# EndLightGate2022.net
KiCad netlist of a schematic drawn in EAGLE
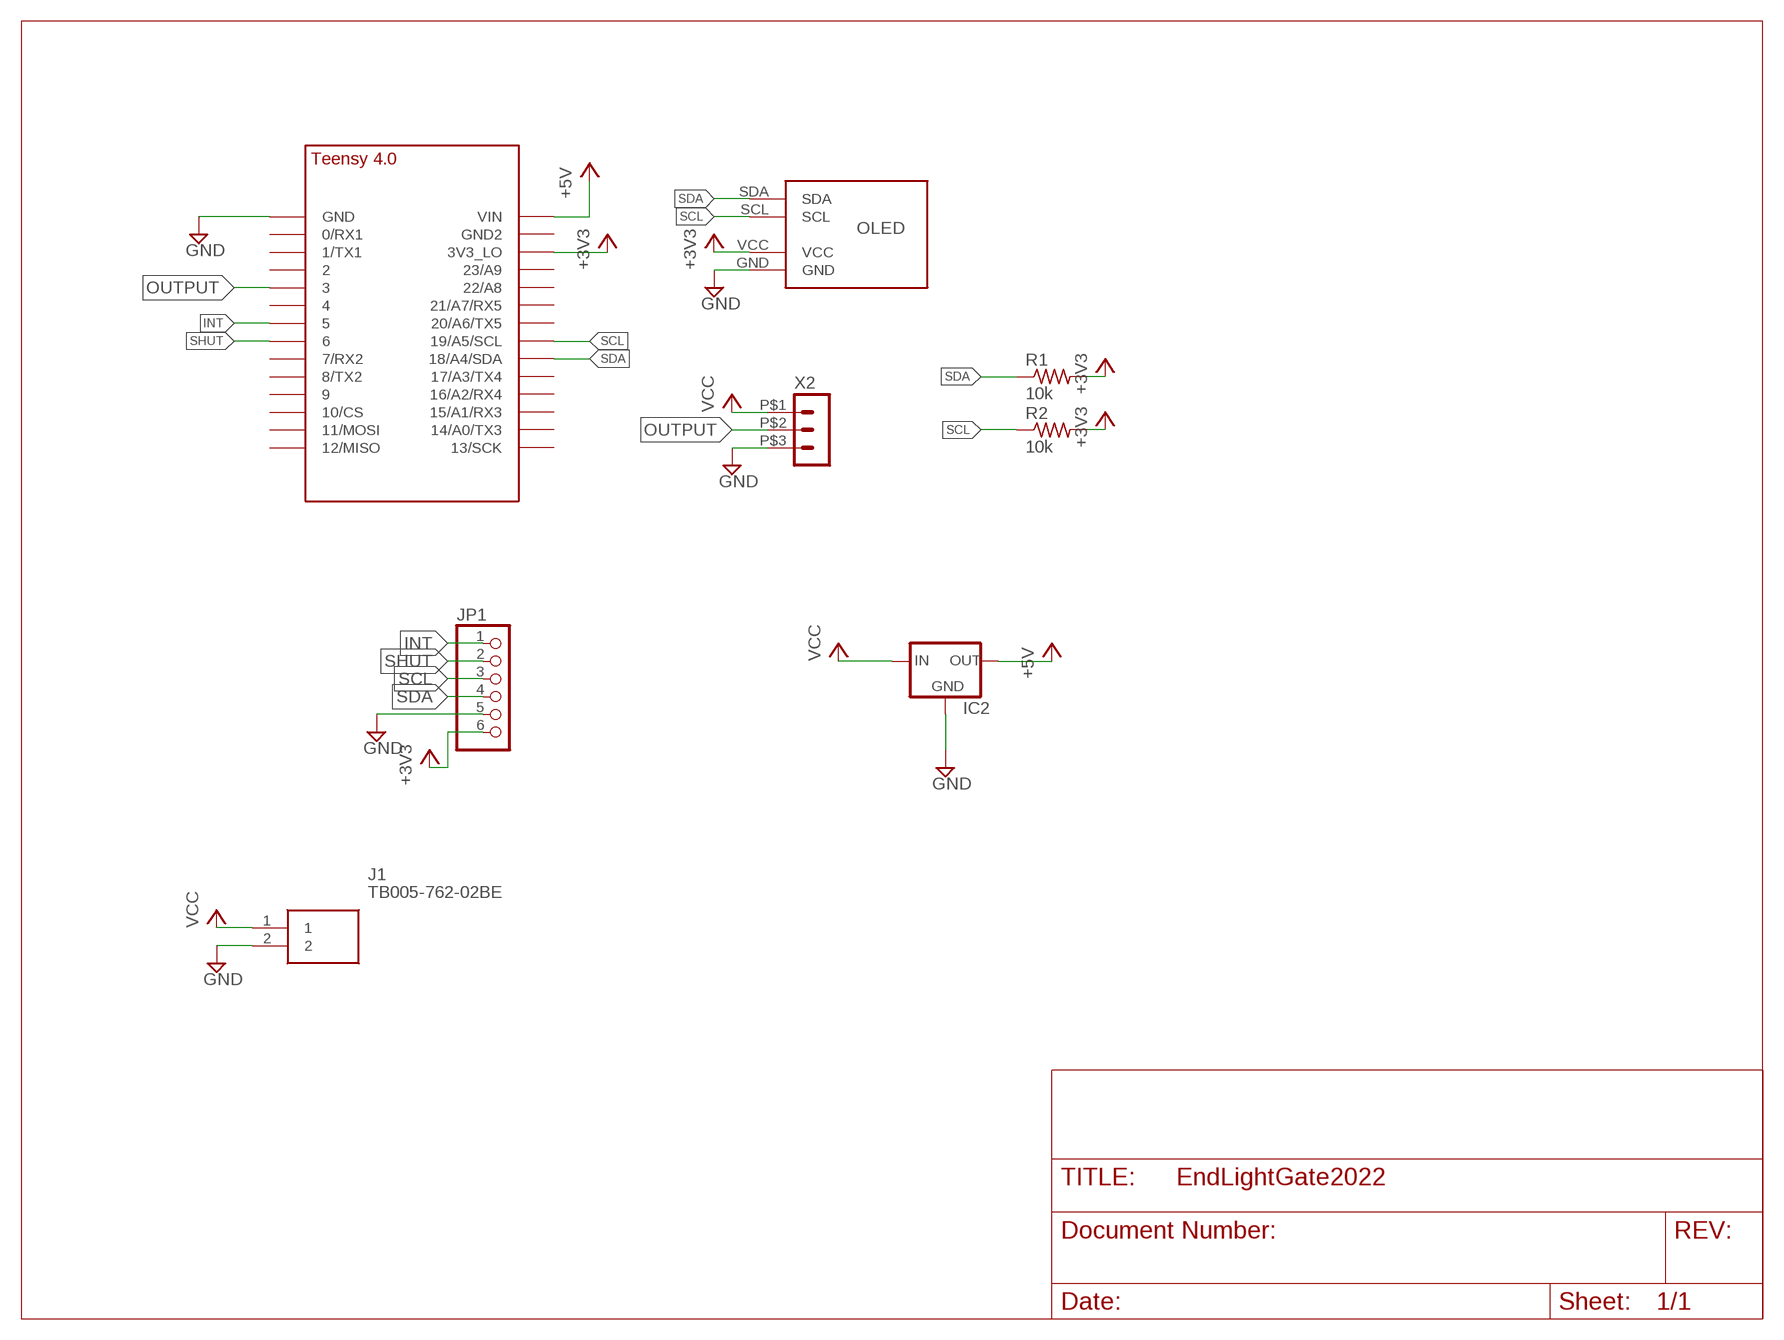
[diagram p0: schematic, sheet 1]

(export (version "E")
  (design (tool "Eeschema 10.0.6"))
  (components
    (comp (ref "IC2")
      (value "REG_5V_L7805_HOR")
      (footprint "eagle-import:TO-220-H")
      (libsource (lib "eagle-import") (part "REG_5V_L7805_HOR"))
    )
    (comp (ref "J1")
      (value "TB005-762-02BE")
      (footprint "eagle-import:TB00576202BE")
      (fields (field (name "MOUSER_PART_NUMBER") "490-TB005-762-02BE"))
      (libsource (lib "eagle-import") (part "TB005-762-02BE"))
    )
    (comp (ref "JP1")
      (value "PINHD-1X6")
      (footprint "eagle-import:1X06")
      (libsource (lib "eagle-import") (part "PINHD-1X6"))
    )
    (comp (ref "R1")
      (value "10k")
      (footprint "eagle-import:1_4W-0.4")
      (libsource (lib "eagle-import") (part "RES_AXIAL1/4W-0.4"))
    )
    (comp (ref "R2")
      (value "10k")
      (footprint "eagle-import:1_4W-0.4")
      (libsource (lib "eagle-import") (part "RES_AXIAL1/4W-0.4"))
    )
    (comp (ref "U$1")
      (value "TEENSY_4.0_SIMPLE")
      (footprint "eagle-import:TEENSY_4.0_SIMPLE")
      (libsource (lib "eagle-import") (part "TEENSY_4.0_SIMPLE"))
    )
    (comp (ref "U$2")
      (value "OLED_SSD1306")
      (footprint "eagle-import:OLED_SSD1306")
      (libsource (lib "eagle-import") (part "OLED_SSD1306"))
    )
    (comp (ref "X2")
      (value "HEADER_POS3_43650-0300")
      (footprint "eagle-import:43650-0300")
      (libsource (lib "eagle-import") (part "HEADER_POS3_?43650-0300"))
    )
  )
  (nets
    (net (code "1") (name "+3V3") (class "Default")
      (node (ref "JP1") (pin "6") (pinfunction "6_6") (pintype "passive"))
      (node (ref "R1") (pin "2") (pinfunction "2_2") (pintype "passive"))
      (node (ref "R2") (pin "2") (pinfunction "2_2") (pintype "passive"))
      (node (ref "U$1") (pin "3V3_LO") (pinfunction "3V3_LO_3V3_LO") (pintype "bidirectional"))
      (node (ref "U$2") (pin "VCC") (pinfunction "VCC_VCC") (pintype "bidirectional"))
    )
    (net (code "2") (name "+5V") (class "Default")
      (node (ref "IC2") (pin "3") (pinfunction "OUT_3") (pintype "output"))
      (node (ref "U$1") (pin "VIN") (pinfunction "VIN_VIN") (pintype "bidirectional"))
    )
    (net (code "3") (name "GND") (class "Default")
      (node (ref "IC2") (pin "2") (pinfunction "GND_2") (pintype "input"))
      (node (ref "J1") (pin "2") (pinfunction "2_2") (pintype "bidirectional"))
      (node (ref "JP1") (pin "5") (pinfunction "5_5") (pintype "passive"))
      (node (ref "U$1") (pin "GND") (pinfunction "GND_GND") (pintype "bidirectional"))
      (node (ref "U$2") (pin "GND") (pinfunction "GND_GND") (pintype "bidirectional"))
      (node (ref "X2") (pin "P$3") (pinfunction "3_P$3") (pintype "passive"))
    )
    (net (code "4") (name "INT") (class "Default")
      (node (ref "JP1") (pin "1") (pinfunction "1_1") (pintype "passive"))
      (node (ref "U$1") (pin "5") (pinfunction "5_5") (pintype "bidirectional"))
    )
    (net (code "5") (name "OUTPUT") (class "Default")
      (node (ref "U$1") (pin "3/CANTX") (pinfunction "3_3/CANTX") (pintype "bidirectional"))
      (node (ref "X2") (pin "P$2") (pinfunction "2_P$2") (pintype "passive"))
    )
    (net (code "6") (name "SCL") (class "Default")
      (node (ref "JP1") (pin "3") (pinfunction "3_3") (pintype "passive"))
      (node (ref "R2") (pin "1") (pinfunction "1_1") (pintype "passive"))
      (node (ref "U$1") (pin "19/A5/SCL") (pinfunction "19/A5/SCL_19/A5/SCL") (pintype "bidirectional"))
      (node (ref "U$2") (pin "SCL") (pinfunction "SCL_SCL") (pintype "bidirectional"))
    )
    (net (code "7") (name "SDA") (class "Default")
      (node (ref "JP1") (pin "4") (pinfunction "4_4") (pintype "passive"))
      (node (ref "R1") (pin "1") (pinfunction "1_1") (pintype "passive"))
      (node (ref "U$1") (pin "18/A4/SDA") (pinfunction "18/A4/SDA_18/A4/SDA") (pintype "bidirectional"))
      (node (ref "U$2") (pin "SDA") (pinfunction "SDA_SDA") (pintype "bidirectional"))
    )
    (net (code "8") (name "SHUT") (class "Default")
      (node (ref "JP1") (pin "2") (pinfunction "2_2") (pintype "passive"))
      (node (ref "U$1") (pin "6") (pinfunction "6_6") (pintype "bidirectional"))
    )
    (net (code "9") (name "VCC") (class "Default")
      (node (ref "IC2") (pin "1") (pinfunction "IN_1") (pintype "input"))
      (node (ref "J1") (pin "1") (pinfunction "1_1") (pintype "bidirectional"))
      (node (ref "X2") (pin "P$1") (pinfunction "1_P$1") (pintype "passive"))
    )
    (net (code "10") (name "unconnected-(U$1-0{slash}RX1-Pad0{slash}RX)") (class "Default")
      (node (ref "U$1") (pin "0/RX") (pinfunction "0/RX1_0/RX") (pintype "bidirectional"))
    )
    (net (code "11") (name "unconnected-(U$1-1{slash}TX1-Pad1{slash}TX)") (class "Default")
      (node (ref "U$1") (pin "1/TX") (pinfunction "1/TX1_1/TX") (pintype "bidirectional"))
    )
    (net (code "12") (name "unconnected-(U$1-4-Pad4{slash}CANRX)") (class "Default")
      (node (ref "U$1") (pin "4/CANRX") (pinfunction "4_4/CANRX") (pintype "bidirectional"))
    )
    (net (code "13") (name "unconnected-(U$1-7{slash}RX2-Pad7)") (class "Default")
      (node (ref "U$1") (pin "7") (pinfunction "7/RX2_7") (pintype "bidirectional"))
    )
    (net (code "14") (name "unconnected-(U$1-8{slash}TX2-Pad8)") (class "Default")
      (node (ref "U$1") (pin "8") (pinfunction "8/TX2_8") (pintype "bidirectional"))
    )
    (net (code "15") (name "unconnected-(U$1-9-Pad9{slash}CS)") (class "Default")
      (node (ref "U$1") (pin "9/CS") (pinfunction "9_9/CS") (pintype "bidirectional"))
    )
    (net (code "16") (name "unconnected-(U$1-14{slash}A0{slash}TX3-Pad14{slash}A0)") (class "Default")
      (node (ref "U$1") (pin "14/A0") (pinfunction "14/A0/TX3_14/A0") (pintype "bidirectional"))
    )
    (net (code "17") (name "unconnected-(U$1-15{slash}A1{slash}RX3-Pad15{slash}A1)") (class "Default")
      (node (ref "U$1") (pin "15/A1") (pinfunction "15/A1/RX3_15/A1") (pintype "bidirectional"))
    )
    (net (code "18") (name "unconnected-(U$1-16{slash}A2{slash}RX4-Pad16{slash}A2)") (class "Default")
      (node (ref "U$1") (pin "16/A2") (pinfunction "16/A2/RX4_16/A2") (pintype "bidirectional"))
    )
    (net (code "19") (name "unconnected-(U$1-17{slash}A3{slash}TX4-Pad17{slash}A3)") (class "Default")
      (node (ref "U$1") (pin "17/A3") (pinfunction "17/A3/TX4_17/A3") (pintype "bidirectional"))
    )
    (net (code "20") (name "unconnected-(U$1-20{slash}A6{slash}TX5-Pad20{slash}A6)") (class "Default")
      (node (ref "U$1") (pin "20/A6") (pinfunction "20/A6/TX5_20/A6") (pintype "bidirectional"))
    )
    (net (code "21") (name "unconnected-(U$1-21{slash}A7{slash}RX5-Pad21{slash}A7)") (class "Default")
      (node (ref "U$1") (pin "21/A7") (pinfunction "21/A7/RX5_21/A7") (pintype "bidirectional"))
    )
    (net (code "22") (name "unconnected-(U$1-Pad2)") (class "Default")
      (node (ref "U$1") (pin "2") (pinfunction "2_2") (pintype "bidirectional"))
    )
    (net (code "23") (name "unconnected-(U$1-Pad10{slash}CS)") (class "Default")
      (node (ref "U$1") (pin "10/CS") (pinfunction "10/CS_10/CS") (pintype "bidirectional"))
    )
    (net (code "24") (name "unconnected-(U$1-Pad11{slash}MOSI)") (class "Default")
      (node (ref "U$1") (pin "11/MOSI") (pinfunction "11/MOSI_11/MOSI") (pintype "bidirectional"))
    )
    (net (code "25") (name "unconnected-(U$1-Pad12{slash}MISO)") (class "Default")
      (node (ref "U$1") (pin "12/MISO") (pinfunction "12/MISO_12/MISO") (pintype "bidirectional"))
    )
    (net (code "26") (name "unconnected-(U$1-Pad13{slash}SCK)") (class "Default")
      (node (ref "U$1") (pin "13/SCK") (pinfunction "13/SCK_13/SCK") (pintype "bidirectional"))
    )
    (net (code "27") (name "unconnected-(U$1-Pad22{slash}A8)") (class "Default")
      (node (ref "U$1") (pin "22/A8") (pinfunction "22/A8_22/A8") (pintype "bidirectional"))
    )
    (net (code "28") (name "unconnected-(U$1-Pad23{slash}A9)") (class "Default")
      (node (ref "U$1") (pin "23/A9") (pinfunction "23/A9_23/A9") (pintype "bidirectional"))
    )
    (net (code "29") (name "unconnected-(U$1-PadGND2)") (class "Default")
      (node (ref "U$1") (pin "GND2") (pinfunction "GND2_GND2") (pintype "bidirectional"))
    )
  )
)
